# 4amppowersupply.net
KiCad netlist of a schematic drawn in EAGLE
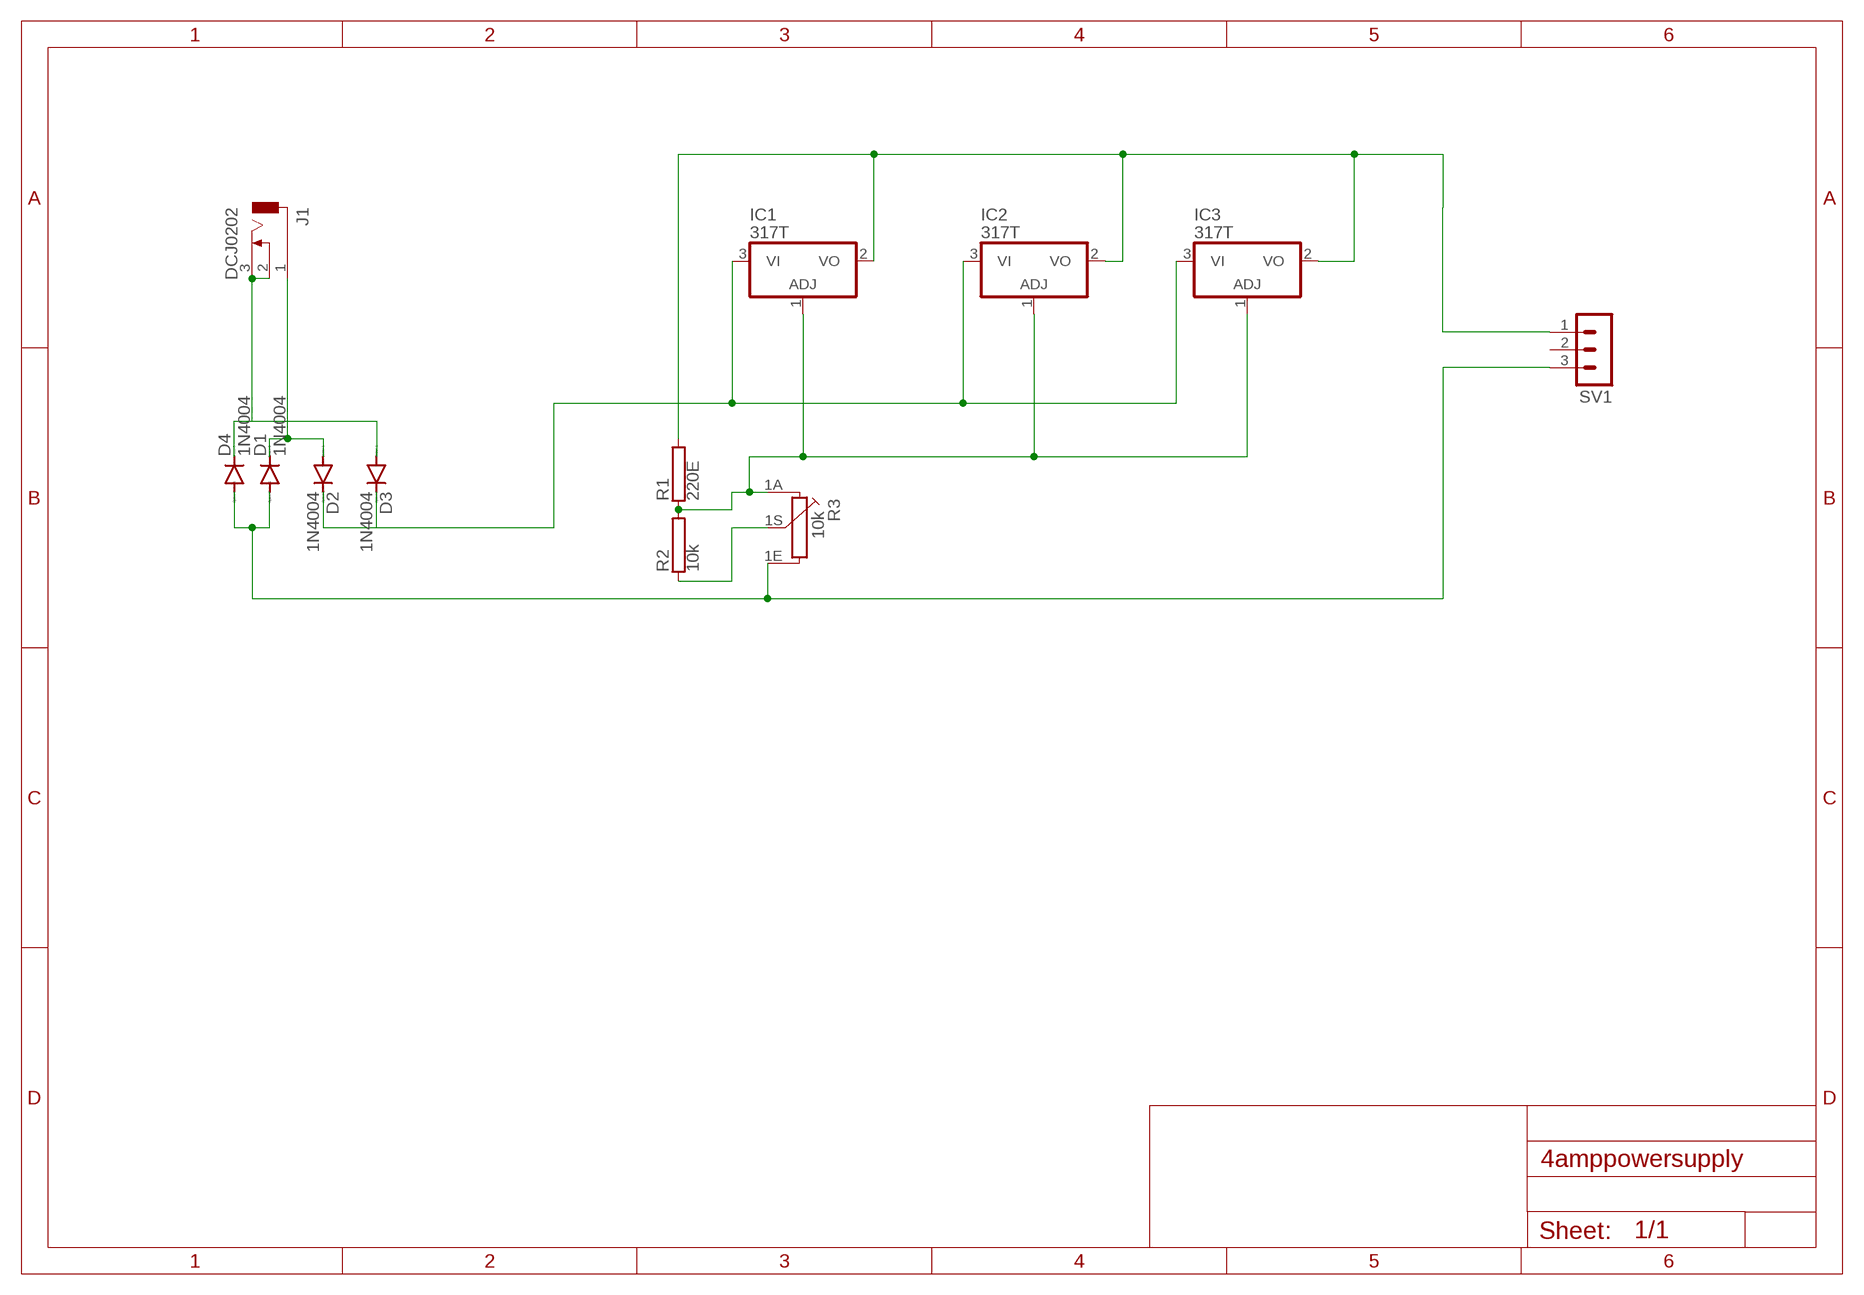
[diagram p0: schematic, sheet 1]

(export (version "E")
  (design (tool "Eeschema 10.0.6"))
  (components
    (comp (ref "D1")
      (value "1N4004")
      (footprint "eagle-import:DO41-10")
      (libsource (lib "eagle-import") (part "1N4004"))
    )
    (comp (ref "D2")
      (value "1N4004")
      (footprint "eagle-import:DO41-10")
      (libsource (lib "eagle-import") (part "1N4004"))
    )
    (comp (ref "D3")
      (value "1N4004")
      (footprint "eagle-import:DO41-10")
      (libsource (lib "eagle-import") (part "1N4004"))
    )
    (comp (ref "D4")
      (value "1N4004")
      (footprint "eagle-import:DO41-10")
      (libsource (lib "eagle-import") (part "1N4004"))
    )
    (comp (ref "IC1")
      (value "317T")
      (footprint "eagle-import:TO220H")
      (libsource (lib "eagle-import") (part "317T"))
    )
    (comp (ref "IC2")
      (value "317T")
      (footprint "eagle-import:TO220H")
      (libsource (lib "eagle-import") (part "317T"))
    )
    (comp (ref "IC3")
      (value "317T")
      (footprint "eagle-import:TO220H")
      (libsource (lib "eagle-import") (part "317T"))
    )
    (comp (ref "J1")
      (value "DCJ0202")
      (footprint "eagle-import:DCJ0202")
      (libsource (lib "eagle-import") (part "DCJ0202"))
    )
    (comp (ref "R1")
      (value "220E")
      (footprint "eagle-import:TO-247-2V")
      (libsource (lib "eagle-import") (part "RMG100-V"))
    )
    (comp (ref "R2")
      (value "10k")
      (footprint "eagle-import:TO-247-2V")
      (libsource (lib "eagle-import") (part "RMG100-V"))
    )
    (comp (ref "R3")
      (value "10k")
      (footprint "eagle-import:PC16S")
      (libsource (lib "eagle-import") (part "PC16S"))
    )
    (comp (ref "SV1")
      (value "MA03-1")
      (footprint "eagle-import:MA03-1")
      (libsource (lib "eagle-import") (part "MA03-1"))
    )
  )
  (nets
    (net (code "1") (name "Net-(D1-PadA)") (class "Default")
      (node (ref "D1") (pin "A") (pinfunction "A_A") (pintype "passive"))
      (node (ref "D4") (pin "A") (pinfunction "A_A") (pintype "passive"))
      (node (ref "R3") (pin "1E") (pinfunction "1E_1E") (pintype "passive"))
      (node (ref "SV1") (pin "3") (pinfunction "3_3") (pintype "passive"))
    )
    (net (code "2") (name "Net-(D1-PadC)") (class "Default")
      (node (ref "D1") (pin "C") (pinfunction "C_C") (pintype "passive"))
      (node (ref "D2") (pin "A") (pinfunction "A_A") (pintype "passive"))
      (node (ref "J1") (pin "1") (pinfunction "1_1") (pintype "passive"))
    )
    (net (code "3") (name "Net-(D3-PadA)") (class "Default")
      (node (ref "D3") (pin "A") (pinfunction "A_A") (pintype "passive"))
      (node (ref "D4") (pin "C") (pinfunction "C_C") (pintype "passive"))
      (node (ref "J1") (pin "2") (pinfunction "2_2") (pintype "passive"))
      (node (ref "J1") (pin "3") (pinfunction "3_3") (pintype "passive"))
    )
    (net (code "4") (name "Net-(IC1-ADJ)") (class "Default")
      (node (ref "IC1") (pin "1") (pinfunction "ADJ_1") (pintype "input"))
      (node (ref "IC2") (pin "1") (pinfunction "ADJ_1") (pintype "input"))
      (node (ref "IC3") (pin "1") (pinfunction "ADJ_1") (pintype "input"))
      (node (ref "R1") (pin "1") (pinfunction "1_1") (pintype "passive"))
      (node (ref "R2") (pin "2") (pinfunction "2_2") (pintype "passive"))
      (node (ref "R3") (pin "1A") (pinfunction "1A_1A") (pintype "passive"))
    )
    (net (code "5") (name "Net-(IC1-VI)") (class "Default")
      (node (ref "D2") (pin "C") (pinfunction "C_C") (pintype "passive"))
      (node (ref "D3") (pin "C") (pinfunction "C_C") (pintype "passive"))
      (node (ref "IC1") (pin "3") (pinfunction "VI_3") (pintype "input"))
      (node (ref "IC2") (pin "3") (pinfunction "VI_3") (pintype "input"))
      (node (ref "IC3") (pin "3") (pinfunction "VI_3") (pintype "input"))
    )
    (net (code "6") (name "Net-(IC1-VO)") (class "Default")
      (node (ref "IC1") (pin "2") (pinfunction "VO_2") (pintype "passive"))
      (node (ref "IC2") (pin "2") (pinfunction "VO_2") (pintype "passive"))
      (node (ref "IC3") (pin "2") (pinfunction "VO_2") (pintype "passive"))
      (node (ref "R1") (pin "2") (pinfunction "2_2") (pintype "passive"))
      (node (ref "SV1") (pin "1") (pinfunction "1_1") (pintype "passive"))
    )
    (net (code "7") (name "Net-(R2-Pad1)") (class "Default")
      (node (ref "R2") (pin "1") (pinfunction "1_1") (pintype "passive"))
      (node (ref "R3") (pin "1S") (pinfunction "1S_1S") (pintype "passive"))
    )
    (net (code "8") (name "unconnected-(SV1-Pad2)") (class "Default")
      (node (ref "SV1") (pin "2") (pinfunction "2_2") (pintype "passive"))
    )
  )
)
